# RatDistortion.net
KiCad netlist of a schematic drawn in EAGLE
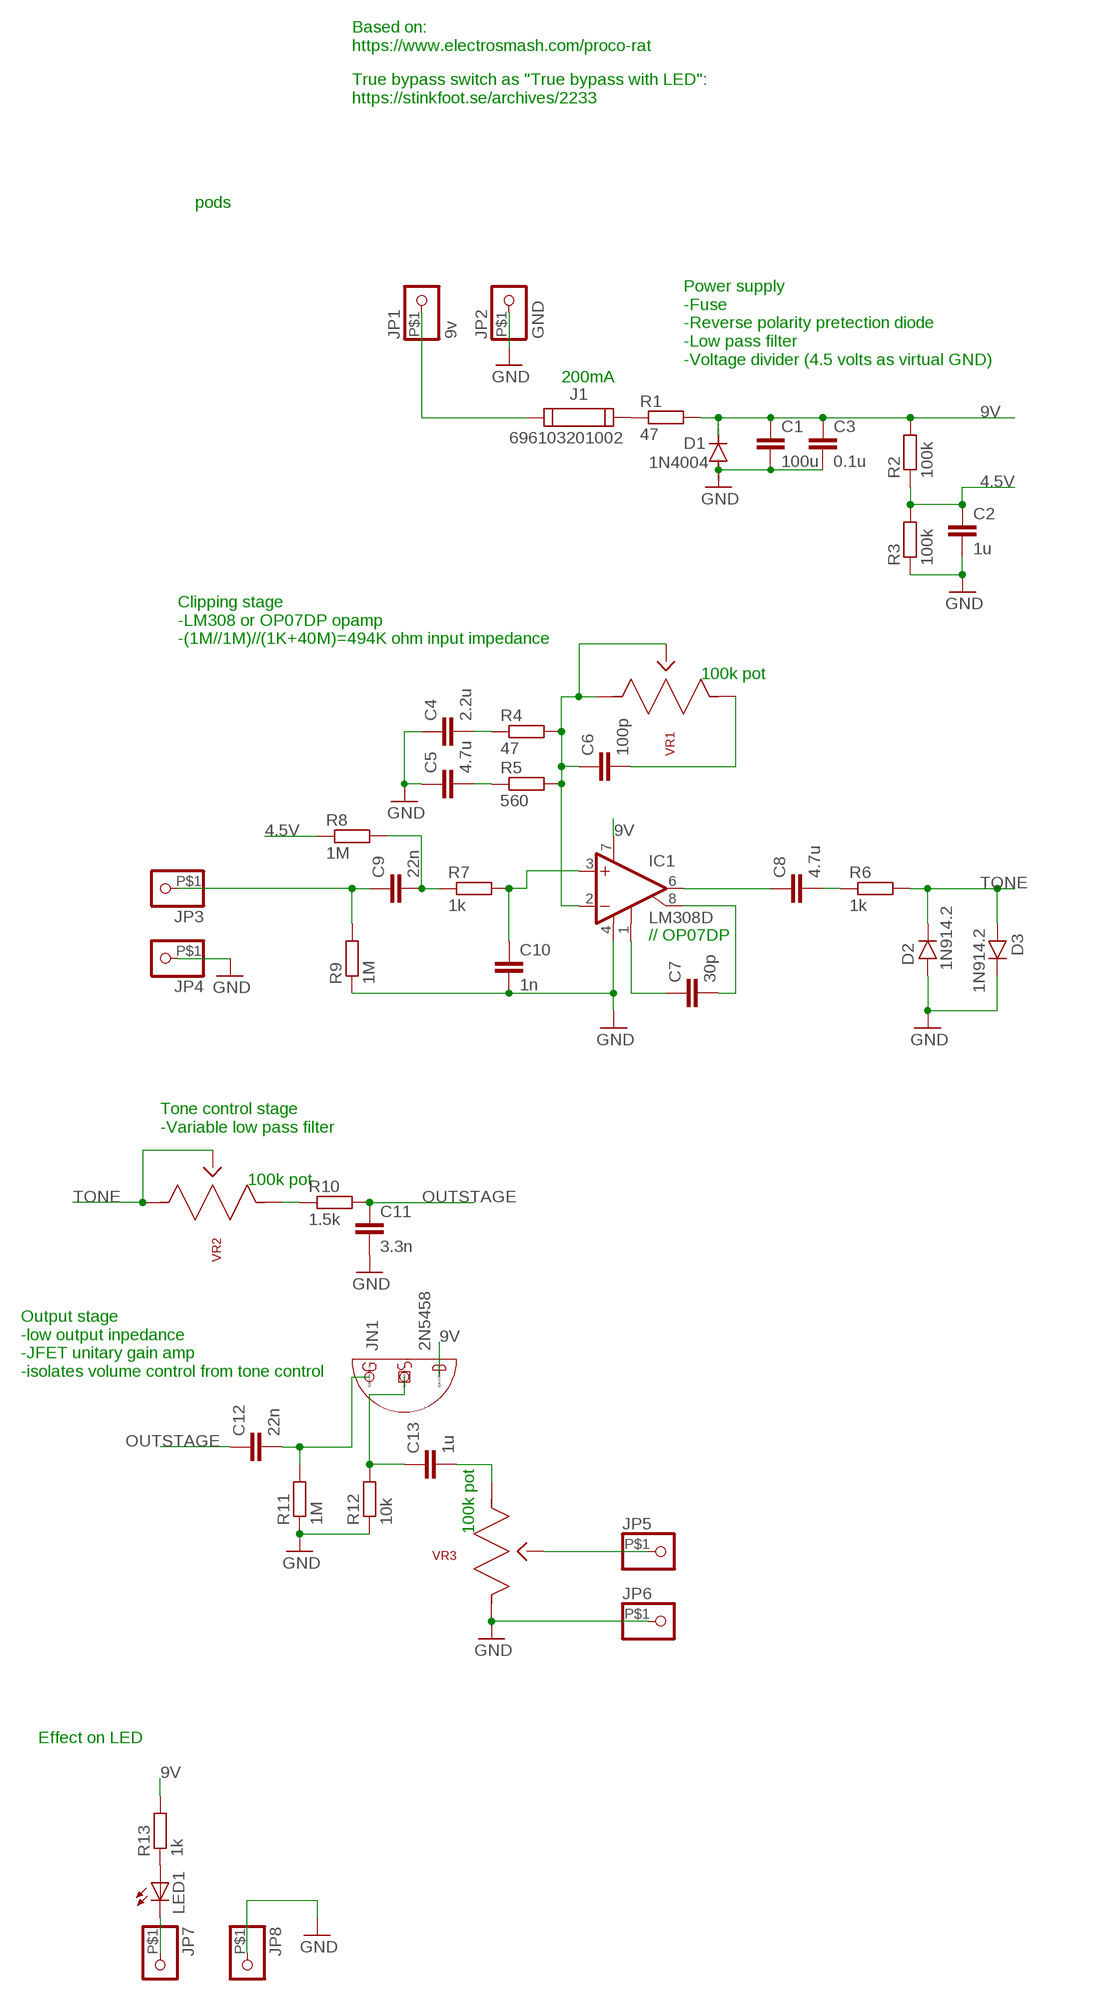
[diagram p0: schematic, sheet 1]

(export (version "E")
  (design (tool "Eeschema 10.0.6"))
  (components
    (comp (ref "C1")
      (value "100u")
      (footprint "eagle-import:C1206")
      (libsource (lib "eagle-import") (part "C-EUC1206"))
    )
    (comp (ref "C2")
      (value "1u")
      (footprint "eagle-import:C1206")
      (libsource (lib "eagle-import") (part "C-EUC1206"))
    )
    (comp (ref "C3")
      (value "0.1u")
      (footprint "eagle-import:C0603")
      (libsource (lib "eagle-import") (part "C-EUC0603"))
    )
    (comp (ref "C4")
      (value "2.2u")
      (footprint "eagle-import:C1206")
      (libsource (lib "eagle-import") (part "C-EUC1206"))
    )
    (comp (ref "C5")
      (value "4.7u")
      (footprint "eagle-import:C1206")
      (libsource (lib "eagle-import") (part "C-EUC1206"))
    )
    (comp (ref "C6")
      (value "100p")
      (footprint "eagle-import:C0603")
      (libsource (lib "eagle-import") (part "C-EUC0603"))
    )
    (comp (ref "C7")
      (value "30p")
      (footprint "eagle-import:C0603")
      (libsource (lib "eagle-import") (part "C-EUC0603"))
    )
    (comp (ref "C8")
      (value "4.7u")
      (footprint "eagle-import:C1206")
      (libsource (lib "eagle-import") (part "C-EUC1206"))
    )
    (comp (ref "C9")
      (value "22n")
      (footprint "eagle-import:C0603")
      (libsource (lib "eagle-import") (part "C-EUC0603"))
    )
    (comp (ref "C10")
      (value "1n")
      (footprint "eagle-import:C0603")
      (libsource (lib "eagle-import") (part "C-EUC0603"))
    )
    (comp (ref "C11")
      (value "3.3n")
      (footprint "eagle-import:C0603")
      (libsource (lib "eagle-import") (part "C-EUC0603"))
    )
    (comp (ref "C12")
      (value "22n")
      (footprint "eagle-import:C0603")
      (libsource (lib "eagle-import") (part "C-EUC0603"))
    )
    (comp (ref "C13")
      (value "1u")
      (footprint "eagle-import:C1206")
      (libsource (lib "eagle-import") (part "C-EUC1206"))
    )
    (comp (ref "D1")
      (value "1N4004")
      (footprint "eagle-import:DO41-10")
      (libsource (lib "eagle-import") (part "1N4004"))
    )
    (comp (ref "D2")
      (value "1N914.2")
      (footprint "eagle-import:DO35-2")
      (fields (field (name "MF") "ON Semiconductor") (field (name "MP") "1N914"))
      (libsource (lib "eagle-import") (part "1N914.2"))
    )
    (comp (ref "D3")
      (value "1N914.2")
      (footprint "eagle-import:DO35-2")
      (fields (field (name "MF") "ON Semiconductor") (field (name "MP") "1N914"))
      (libsource (lib "eagle-import") (part "1N914.2"))
    )
    (comp (ref "IC1")
      (value "LM308D")
      (footprint "eagle-import:SO08")
      (libsource (lib "eagle-import") (part "LM308D"))
    )
    (comp (ref "J1")
      (value "696103201002")
      (footprint "eagle-import:696103201002")
      (fields (field (name "MF") "Wurth Electronics"))
      (libsource (lib "eagle-import") (part "696103201002"))
    )
    (comp (ref "JN1")
      (value "2N5458")
      (footprint "eagle-import:TO92")
      (fields (field (name "MF") "ON Semiconductor"))
      (libsource (lib "eagle-import") (part "2N5458"))
    )
    (comp (ref "JP1")
      (value "9v")
      (footprint "eagle-import:1X1-BIGPOGO")
      (libsource (lib "eagle-import") (part "PINHD-1X1-BIGPOGO"))
    )
    (comp (ref "JP2")
      (value "GND")
      (footprint "eagle-import:1X1-BIGPOGO")
      (libsource (lib "eagle-import") (part "PINHD-1X1-BIGPOGO"))
    )
    (comp (ref "JP3")
      (value "PINHD-1X1-BIGPOGO")
      (footprint "eagle-import:1X1-BIGPOGO")
      (libsource (lib "eagle-import") (part "PINHD-1X1-BIGPOGO"))
    )
    (comp (ref "JP4")
      (value "PINHD-1X1-BIGPOGO")
      (footprint "eagle-import:1X1-BIGPOGO")
      (libsource (lib "eagle-import") (part "PINHD-1X1-BIGPOGO"))
    )
    (comp (ref "JP5")
      (value "PINHD-1X1-BIGPOGO")
      (footprint "eagle-import:1X1-BIGPOGO")
      (libsource (lib "eagle-import") (part "PINHD-1X1-BIGPOGO"))
    )
    (comp (ref "JP6")
      (value "PINHD-1X1-BIGPOGO")
      (footprint "eagle-import:1X1-BIGPOGO")
      (libsource (lib "eagle-import") (part "PINHD-1X1-BIGPOGO"))
    )
    (comp (ref "JP7")
      (value "PINHD-1X1-BIGPOGO")
      (footprint "eagle-import:1X1-BIGPOGO")
      (libsource (lib "eagle-import") (part "PINHD-1X1-BIGPOGO"))
    )
    (comp (ref "JP8")
      (value "PINHD-1X1-BIGPOGO")
      (footprint "eagle-import:1X1-BIGPOGO")
      (libsource (lib "eagle-import") (part "PINHD-1X1-BIGPOGO"))
    )
    (comp (ref "LED1")
      (value "LED3MM")
      (footprint "eagle-import:LED3MM")
      (libsource (lib "eagle-import") (part "LED3MM"))
    )
    (comp (ref "R1")
      (value "47")
      (footprint "eagle-import:R0603")
      (libsource (lib "eagle-import") (part "R-EU_R0603"))
    )
    (comp (ref "R2")
      (value "100k")
      (footprint "eagle-import:R0603")
      (libsource (lib "eagle-import") (part "R-EU_R0603"))
    )
    (comp (ref "R3")
      (value "100k")
      (footprint "eagle-import:R0603")
      (libsource (lib "eagle-import") (part "R-EU_R0603"))
    )
    (comp (ref "R4")
      (value "47")
      (footprint "eagle-import:R0603")
      (libsource (lib "eagle-import") (part "R-EU_R0603"))
    )
    (comp (ref "R5")
      (value "560")
      (footprint "eagle-import:R0603")
      (libsource (lib "eagle-import") (part "R-EU_R0603"))
    )
    (comp (ref "R6")
      (value "1k")
      (footprint "eagle-import:R0603")
      (libsource (lib "eagle-import") (part "R-EU_R0603"))
    )
    (comp (ref "R7")
      (value "1k")
      (footprint "eagle-import:R0603")
      (libsource (lib "eagle-import") (part "R-EU_R0603"))
    )
    (comp (ref "R8")
      (value "1M")
      (footprint "eagle-import:R0603")
      (libsource (lib "eagle-import") (part "R-EU_R0603"))
    )
    (comp (ref "R9")
      (value "1M")
      (footprint "eagle-import:R0603")
      (libsource (lib "eagle-import") (part "R-EU_R0603"))
    )
    (comp (ref "R10")
      (value "1.5k")
      (footprint "eagle-import:R0603")
      (libsource (lib "eagle-import") (part "R-EU_R0603"))
    )
    (comp (ref "R11")
      (value "1M")
      (footprint "eagle-import:R0603")
      (libsource (lib "eagle-import") (part "R-EU_R0603"))
    )
    (comp (ref "R12")
      (value "10k")
      (footprint "eagle-import:R0603")
      (libsource (lib "eagle-import") (part "R-EU_R0603"))
    )
    (comp (ref "R13")
      (value "1k")
      (footprint "eagle-import:R0603")
      (libsource (lib "eagle-import") (part "R-EU_R0603"))
    )
    (comp (ref "VR1")
      (value "PTV09A-4225F-B104")
      (footprint "eagle-import:PTV09")
      (fields (field (name "MF") "Bourns"))
      (libsource (lib "eagle-import") (part "PTV09A-4225F-B104"))
    )
    (comp (ref "VR2")
      (value "PTV09A-4225F-B104")
      (footprint "eagle-import:PTV09")
      (fields (field (name "MF") "Bourns"))
      (libsource (lib "eagle-import") (part "PTV09A-4225F-B104"))
    )
    (comp (ref "VR3")
      (value "PTV09A-4225F-B104")
      (footprint "eagle-import:PTV09")
      (fields (field (name "MF") "Bourns"))
      (libsource (lib "eagle-import") (part "PTV09A-4225F-B104"))
    )
  )
  (nets
    (net (code "1") (name "/4.5V") (class "Default")
      (node (ref "C2") (pin "1") (pinfunction "1_1") (pintype "passive"))
      (node (ref "R2") (pin "1") (pinfunction "1_1") (pintype "passive"))
      (node (ref "R3") (pin "2") (pinfunction "2_2") (pintype "passive"))
      (node (ref "R8") (pin "1") (pinfunction "1_1") (pintype "passive"))
    )
    (net (code "2") (name "/9V") (class "Default")
      (node (ref "C1") (pin "1") (pinfunction "1_1") (pintype "passive"))
      (node (ref "C3") (pin "1") (pinfunction "1_1") (pintype "passive"))
      (node (ref "D1") (pin "C") (pinfunction "C_C") (pintype "passive"))
      (node (ref "IC1") (pin "7") (pinfunction "V+_7") (pintype "power_in"))
      (node (ref "JN1") (pin "3") (pinfunction "D_3") (pintype "passive"))
      (node (ref "R1") (pin "2") (pinfunction "2_2") (pintype "passive"))
      (node (ref "R13") (pin "2") (pinfunction "2_2") (pintype "passive"))
      (node (ref "R2") (pin "2") (pinfunction "2_2") (pintype "passive"))
    )
    (net (code "3") (name "/OUTSTAGE") (class "Default")
      (node (ref "C11") (pin "1") (pinfunction "1_1") (pintype "passive"))
      (node (ref "C12") (pin "1") (pinfunction "1_1") (pintype "passive"))
      (node (ref "R10") (pin "2") (pinfunction "2_2") (pintype "passive"))
    )
    (net (code "4") (name "/TONE") (class "Default")
      (node (ref "D2") (pin "C") (pinfunction "C_C") (pintype "passive"))
      (node (ref "D3") (pin "A") (pinfunction "A_A") (pintype "passive"))
      (node (ref "R6") (pin "2") (pinfunction "2_2") (pintype "passive"))
      (node (ref "VR2") (pin "2") (pinfunction "2_2") (pintype "bidirectional"))
      (node (ref "VR2") (pin "3") (pinfunction "3_3") (pintype "bidirectional"))
    )
    (net (code "5") (name "GND") (class "Default")
      (node (ref "C1") (pin "2") (pinfunction "2_2") (pintype "passive"))
      (node (ref "C10") (pin "2") (pinfunction "2_2") (pintype "passive"))
      (node (ref "C11") (pin "2") (pinfunction "2_2") (pintype "passive"))
      (node (ref "C2") (pin "2") (pinfunction "2_2") (pintype "passive"))
      (node (ref "C3") (pin "2") (pinfunction "2_2") (pintype "passive"))
      (node (ref "C4") (pin "1") (pinfunction "1_1") (pintype "passive"))
      (node (ref "C5") (pin "1") (pinfunction "1_1") (pintype "passive"))
      (node (ref "D1") (pin "A") (pinfunction "A_A") (pintype "passive"))
      (node (ref "D2") (pin "A") (pinfunction "A_A") (pintype "passive"))
      (node (ref "D3") (pin "C") (pinfunction "C_C") (pintype "passive"))
      (node (ref "IC1") (pin "4") (pinfunction "V-_4") (pintype "power_in"))
      (node (ref "JP2") (pin "P$1") (pinfunction "1_P$1") (pintype "passive"))
      (node (ref "JP4") (pin "P$1") (pinfunction "1_P$1") (pintype "passive"))
      (node (ref "JP6") (pin "P$1") (pinfunction "1_P$1") (pintype "passive"))
      (node (ref "JP8") (pin "P$1") (pinfunction "1_P$1") (pintype "passive"))
      (node (ref "R11") (pin "1") (pinfunction "1_1") (pintype "passive"))
      (node (ref "R12") (pin "1") (pinfunction "1_1") (pintype "passive"))
      (node (ref "R3") (pin "1") (pinfunction "1_1") (pintype "passive"))
      (node (ref "R9") (pin "1") (pinfunction "1_1") (pintype "passive"))
      (node (ref "VR3") (pin "1") (pinfunction "1_1") (pintype "bidirectional"))
    )
    (net (code "6") (name "Net-(C4-Pad2)") (class "Default")
      (node (ref "C4") (pin "2") (pinfunction "2_2") (pintype "passive"))
      (node (ref "R4") (pin "1") (pinfunction "1_1") (pintype "passive"))
    )
    (net (code "7") (name "Net-(C5-Pad2)") (class "Default")
      (node (ref "C5") (pin "2") (pinfunction "2_2") (pintype "passive"))
      (node (ref "R5") (pin "1") (pinfunction "1_1") (pintype "passive"))
    )
    (net (code "8") (name "Net-(C6-Pad2)") (class "Default")
      (node (ref "C6") (pin "2") (pinfunction "2_2") (pintype "passive"))
      (node (ref "VR1") (pin "1") (pinfunction "1_1") (pintype "bidirectional"))
    )
    (net (code "9") (name "Net-(C8-Pad2)") (class "Default")
      (node (ref "C8") (pin "2") (pinfunction "2_2") (pintype "passive"))
      (node (ref "R6") (pin "1") (pinfunction "1_1") (pintype "passive"))
    )
    (net (code "10") (name "Net-(C9-Pad2)") (class "Default")
      (node (ref "C9") (pin "2") (pinfunction "2_2") (pintype "passive"))
      (node (ref "R7") (pin "1") (pinfunction "1_1") (pintype "passive"))
      (node (ref "R8") (pin "2") (pinfunction "2_2") (pintype "passive"))
    )
    (net (code "11") (name "Net-(C13-Pad2)") (class "Default")
      (node (ref "C13") (pin "2") (pinfunction "2_2") (pintype "passive"))
      (node (ref "VR3") (pin "3") (pinfunction "3_3") (pintype "bidirectional"))
    )
    (net (code "12") (name "Net-(IC1-+IN)") (class "Default")
      (node (ref "C10") (pin "1") (pinfunction "1_1") (pintype "passive"))
      (node (ref "IC1") (pin "3") (pinfunction "+IN_3") (pintype "input"))
      (node (ref "R7") (pin "2") (pinfunction "2_2") (pintype "passive"))
    )
    (net (code "13") (name "Net-(IC1--IN)") (class "Default")
      (node (ref "C6") (pin "1") (pinfunction "1_1") (pintype "passive"))
      (node (ref "IC1") (pin "2") (pinfunction "-IN_2") (pintype "input"))
      (node (ref "R4") (pin "2") (pinfunction "2_2") (pintype "passive"))
      (node (ref "R5") (pin "2") (pinfunction "2_2") (pintype "passive"))
      (node (ref "VR1") (pin "2") (pinfunction "2_2") (pintype "bidirectional"))
      (node (ref "VR1") (pin "3") (pinfunction "3_3") (pintype "bidirectional"))
    )
    (net (code "14") (name "Net-(IC1-CMP1)") (class "Default")
      (node (ref "C7") (pin "1") (pinfunction "1_1") (pintype "passive"))
      (node (ref "IC1") (pin "1") (pinfunction "CMP1_1") (pintype "passive"))
    )
    (net (code "15") (name "Net-(IC1-CMP2)") (class "Default")
      (node (ref "C7") (pin "2") (pinfunction "2_2") (pintype "passive"))
      (node (ref "IC1") (pin "8") (pinfunction "CMP2_8") (pintype "passive"))
    )
    (net (code "16") (name "Net-(IC1-OUT)") (class "Default")
      (node (ref "C8") (pin "1") (pinfunction "1_1") (pintype "passive"))
      (node (ref "IC1") (pin "6") (pinfunction "OUT_6") (pintype "output"))
    )
    (net (code "17") (name "Net-(J1-Pad2)") (class "Default")
      (node (ref "J1") (pin "2") (pinfunction "2_2") (pintype "passive"))
      (node (ref "R1") (pin "1") (pinfunction "1_1") (pintype "passive"))
    )
    (net (code "18") (name "Net-(JN1-G)") (class "Default")
      (node (ref "C12") (pin "2") (pinfunction "2_2") (pintype "passive"))
      (node (ref "JN1") (pin "1") (pinfunction "G_1") (pintype "passive"))
      (node (ref "R11") (pin "2") (pinfunction "2_2") (pintype "passive"))
    )
    (net (code "19") (name "Net-(JN1-S)") (class "Default")
      (node (ref "C13") (pin "1") (pinfunction "1_1") (pintype "passive"))
      (node (ref "JN1") (pin "2") (pinfunction "S_2") (pintype "passive"))
      (node (ref "R12") (pin "2") (pinfunction "2_2") (pintype "passive"))
    )
    (net (code "20") (name "Net-(JP1-1)") (class "Default")
      (node (ref "J1") (pin "1") (pinfunction "1_1") (pintype "passive"))
      (node (ref "JP1") (pin "P$1") (pinfunction "1_P$1") (pintype "passive"))
    )
    (net (code "21") (name "Net-(JP3-1)") (class "Default")
      (node (ref "C9") (pin "1") (pinfunction "1_1") (pintype "passive"))
      (node (ref "JP3") (pin "P$1") (pinfunction "1_P$1") (pintype "passive"))
      (node (ref "R9") (pin "2") (pinfunction "2_2") (pintype "passive"))
    )
    (net (code "22") (name "Net-(JP5-1)") (class "Default")
      (node (ref "JP5") (pin "P$1") (pinfunction "1_P$1") (pintype "passive"))
      (node (ref "VR3") (pin "2") (pinfunction "2_2") (pintype "bidirectional"))
    )
    (net (code "23") (name "Net-(JP7-1)") (class "Default")
      (node (ref "JP7") (pin "P$1") (pinfunction "1_P$1") (pintype "passive"))
      (node (ref "LED1") (pin "K") (pinfunction "C_K") (pintype "passive"))
    )
    (net (code "24") (name "Net-(LED1-PadA)") (class "Default")
      (node (ref "LED1") (pin "A") (pinfunction "A_A") (pintype "passive"))
      (node (ref "R13") (pin "1") (pinfunction "1_1") (pintype "passive"))
    )
    (net (code "25") (name "Net-(R10-Pad1)") (class "Default")
      (node (ref "R10") (pin "1") (pinfunction "1_1") (pintype "passive"))
      (node (ref "VR2") (pin "1") (pinfunction "1_1") (pintype "bidirectional"))
    )
  )
)
